# Met.net
KiCad netlist of a schematic drawn in EAGLE
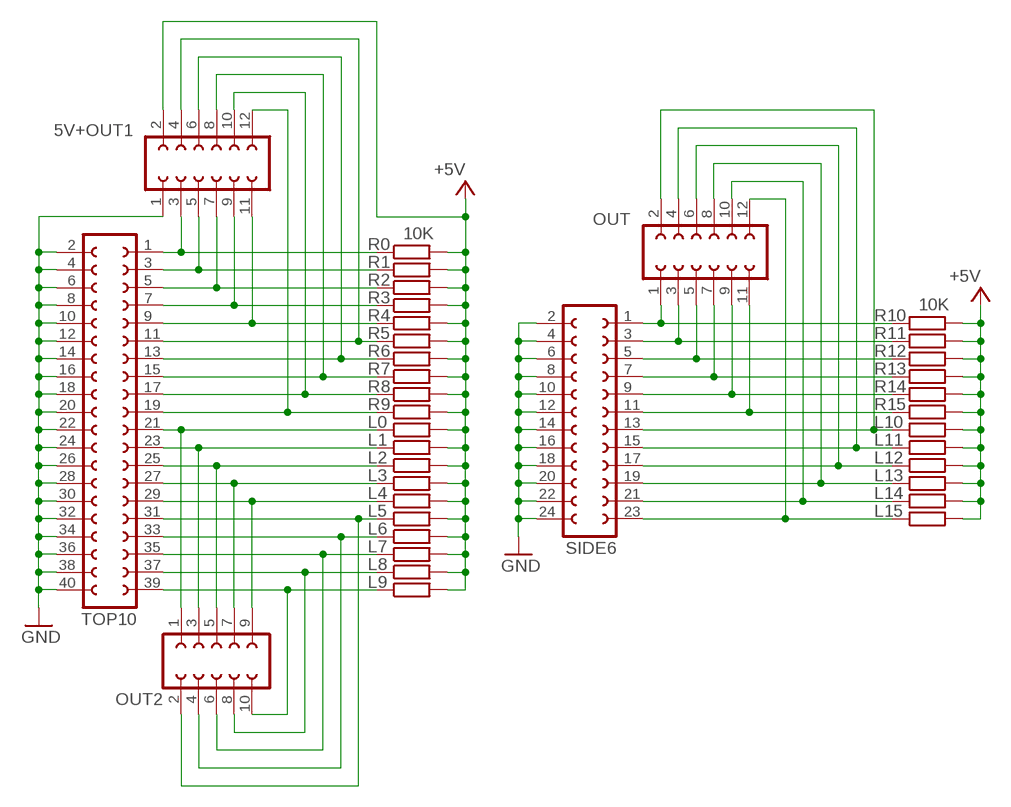
[diagram p0: schematic, sheet 1]

(export (version "E")
  (design (tool "Eeschema 10.0.6"))
  (components
    (comp (ref "5V+OUT1")
      (value "FE06-2")
      (footprint "eagle-import:FE06-2")
      (libsource (lib "eagle-import") (part "FE06-2"))
    )
    (comp (ref "L0")
      (value "R-EU_0207/10")
      (footprint "eagle-import:0207_10")
      (libsource (lib "eagle-import") (part "R-EU_0207/10"))
    )
    (comp (ref "L1")
      (value "R-EU_0207/10")
      (footprint "eagle-import:0207_10")
      (libsource (lib "eagle-import") (part "R-EU_0207/10"))
    )
    (comp (ref "L2")
      (value "R-EU_0207/10")
      (footprint "eagle-import:0207_10")
      (libsource (lib "eagle-import") (part "R-EU_0207/10"))
    )
    (comp (ref "L3")
      (value "R-EU_0207/10")
      (footprint "eagle-import:0207_10")
      (libsource (lib "eagle-import") (part "R-EU_0207/10"))
    )
    (comp (ref "L4")
      (value "R-EU_0207/10")
      (footprint "eagle-import:0207_10")
      (libsource (lib "eagle-import") (part "R-EU_0207/10"))
    )
    (comp (ref "L5")
      (value "R-EU_0207/10")
      (footprint "eagle-import:0207_10")
      (libsource (lib "eagle-import") (part "R-EU_0207/10"))
    )
    (comp (ref "L6")
      (value "R-EU_0207/10")
      (footprint "eagle-import:0207_10")
      (libsource (lib "eagle-import") (part "R-EU_0207/10"))
    )
    (comp (ref "L7")
      (value "R-EU_0207/10")
      (footprint "eagle-import:0207_10")
      (libsource (lib "eagle-import") (part "R-EU_0207/10"))
    )
    (comp (ref "L8")
      (value "R-EU_0207/10")
      (footprint "eagle-import:0207_10")
      (libsource (lib "eagle-import") (part "R-EU_0207/10"))
    )
    (comp (ref "L9")
      (value "R-EU_0207/10")
      (footprint "eagle-import:0207_10")
      (libsource (lib "eagle-import") (part "R-EU_0207/10"))
    )
    (comp (ref "L10")
      (value "R-EU_0207/10")
      (footprint "eagle-import:0207_10")
      (libsource (lib "eagle-import") (part "R-EU_0207/10"))
    )
    (comp (ref "L11")
      (value "R-EU_0207/10")
      (footprint "eagle-import:0207_10")
      (libsource (lib "eagle-import") (part "R-EU_0207/10"))
    )
    (comp (ref "L12")
      (value "R-EU_0207/10")
      (footprint "eagle-import:0207_10")
      (libsource (lib "eagle-import") (part "R-EU_0207/10"))
    )
    (comp (ref "L13")
      (value "R-EU_0207/10")
      (footprint "eagle-import:0207_10")
      (libsource (lib "eagle-import") (part "R-EU_0207/10"))
    )
    (comp (ref "L14")
      (value "R-EU_0207/10")
      (footprint "eagle-import:0207_10")
      (libsource (lib "eagle-import") (part "R-EU_0207/10"))
    )
    (comp (ref "L15")
      (value "R-EU_0207/10")
      (footprint "eagle-import:0207_10")
      (libsource (lib "eagle-import") (part "R-EU_0207/10"))
    )
    (comp (ref "OUT")
      (value "FE06-2")
      (footprint "eagle-import:FE06-2")
      (libsource (lib "eagle-import") (part "FE06-2"))
    )
    (comp (ref "OUT2")
      (value "FE05-2")
      (footprint "eagle-import:FE05-2")
      (libsource (lib "eagle-import") (part "FE05-2"))
    )
    (comp (ref "R0")
      (value "10K")
      (footprint "eagle-import:0207_10")
      (libsource (lib "eagle-import") (part "R-EU_0207/10"))
    )
    (comp (ref "R1")
      (value "R-EU_0207/10")
      (footprint "eagle-import:0207_10")
      (libsource (lib "eagle-import") (part "R-EU_0207/10"))
    )
    (comp (ref "R2")
      (value "R-EU_0207/10")
      (footprint "eagle-import:0207_10")
      (libsource (lib "eagle-import") (part "R-EU_0207/10"))
    )
    (comp (ref "R3")
      (value "R-EU_0207/10")
      (footprint "eagle-import:0207_10")
      (libsource (lib "eagle-import") (part "R-EU_0207/10"))
    )
    (comp (ref "R4")
      (value "R-EU_0207/10")
      (footprint "eagle-import:0207_10")
      (libsource (lib "eagle-import") (part "R-EU_0207/10"))
    )
    (comp (ref "R5")
      (value "R-EU_0207/10")
      (footprint "eagle-import:0207_10")
      (libsource (lib "eagle-import") (part "R-EU_0207/10"))
    )
    (comp (ref "R6")
      (value "R-EU_0207/10")
      (footprint "eagle-import:0207_10")
      (libsource (lib "eagle-import") (part "R-EU_0207/10"))
    )
    (comp (ref "R7")
      (value "R-EU_0207/10")
      (footprint "eagle-import:0207_10")
      (libsource (lib "eagle-import") (part "R-EU_0207/10"))
    )
    (comp (ref "R8")
      (value "R-EU_0207/10")
      (footprint "eagle-import:0207_10")
      (libsource (lib "eagle-import") (part "R-EU_0207/10"))
    )
    (comp (ref "R9")
      (value "R-EU_0207/10")
      (footprint "eagle-import:0207_10")
      (libsource (lib "eagle-import") (part "R-EU_0207/10"))
    )
    (comp (ref "R10")
      (value "10K")
      (footprint "eagle-import:0207_10")
      (libsource (lib "eagle-import") (part "R-EU_0207/10"))
    )
    (comp (ref "R11")
      (value "R-EU_0207/10")
      (footprint "eagle-import:0207_10")
      (libsource (lib "eagle-import") (part "R-EU_0207/10"))
    )
    (comp (ref "R12")
      (value "R-EU_0207/10")
      (footprint "eagle-import:0207_10")
      (libsource (lib "eagle-import") (part "R-EU_0207/10"))
    )
    (comp (ref "R13")
      (value "R-EU_0207/10")
      (footprint "eagle-import:0207_10")
      (libsource (lib "eagle-import") (part "R-EU_0207/10"))
    )
    (comp (ref "R14")
      (value "R-EU_0207/10")
      (footprint "eagle-import:0207_10")
      (libsource (lib "eagle-import") (part "R-EU_0207/10"))
    )
    (comp (ref "R15")
      (value "R-EU_0207/10")
      (footprint "eagle-import:0207_10")
      (libsource (lib "eagle-import") (part "R-EU_0207/10"))
    )
    (comp (ref "SIDE6")
      (value "FE12-2")
      (footprint "eagle-import:FE12-2")
      (libsource (lib "eagle-import") (part "FE12-2"))
    )
    (comp (ref "TOP10")
      (value "FE20-2")
      (footprint "eagle-import:FE20-2")
      (libsource (lib "eagle-import") (part "FE20-2"))
    )
  )
  (nets
    (net (code "1") (name "+5V") (class "Default")
      (node (ref "5V+OUT1") (pin "2") (pinfunction "2_2") (pintype "passive"))
      (node (ref "L0") (pin "2") (pinfunction "2_2") (pintype "passive"))
      (node (ref "L1") (pin "2") (pinfunction "2_2") (pintype "passive"))
      (node (ref "L10") (pin "2") (pinfunction "2_2") (pintype "passive"))
      (node (ref "L11") (pin "2") (pinfunction "2_2") (pintype "passive"))
      (node (ref "L12") (pin "2") (pinfunction "2_2") (pintype "passive"))
      (node (ref "L13") (pin "2") (pinfunction "2_2") (pintype "passive"))
      (node (ref "L14") (pin "2") (pinfunction "2_2") (pintype "passive"))
      (node (ref "L15") (pin "2") (pinfunction "2_2") (pintype "passive"))
      (node (ref "L2") (pin "2") (pinfunction "2_2") (pintype "passive"))
      (node (ref "L3") (pin "2") (pinfunction "2_2") (pintype "passive"))
      (node (ref "L4") (pin "2") (pinfunction "2_2") (pintype "passive"))
      (node (ref "L5") (pin "2") (pinfunction "2_2") (pintype "passive"))
      (node (ref "L6") (pin "2") (pinfunction "2_2") (pintype "passive"))
      (node (ref "L7") (pin "2") (pinfunction "2_2") (pintype "passive"))
      (node (ref "L8") (pin "2") (pinfunction "2_2") (pintype "passive"))
      (node (ref "L9") (pin "2") (pinfunction "2_2") (pintype "passive"))
      (node (ref "R0") (pin "2") (pinfunction "2_2") (pintype "passive"))
      (node (ref "R1") (pin "2") (pinfunction "2_2") (pintype "passive"))
      (node (ref "R10") (pin "2") (pinfunction "2_2") (pintype "passive"))
      (node (ref "R11") (pin "2") (pinfunction "2_2") (pintype "passive"))
      (node (ref "R12") (pin "2") (pinfunction "2_2") (pintype "passive"))
      (node (ref "R13") (pin "2") (pinfunction "2_2") (pintype "passive"))
      (node (ref "R14") (pin "2") (pinfunction "2_2") (pintype "passive"))
      (node (ref "R15") (pin "2") (pinfunction "2_2") (pintype "passive"))
      (node (ref "R2") (pin "2") (pinfunction "2_2") (pintype "passive"))
      (node (ref "R3") (pin "2") (pinfunction "2_2") (pintype "passive"))
      (node (ref "R4") (pin "2") (pinfunction "2_2") (pintype "passive"))
      (node (ref "R5") (pin "2") (pinfunction "2_2") (pintype "passive"))
      (node (ref "R6") (pin "2") (pinfunction "2_2") (pintype "passive"))
      (node (ref "R7") (pin "2") (pinfunction "2_2") (pintype "passive"))
      (node (ref "R8") (pin "2") (pinfunction "2_2") (pintype "passive"))
      (node (ref "R9") (pin "2") (pinfunction "2_2") (pintype "passive"))
    )
    (net (code "2") (name "GND") (class "Default")
      (node (ref "5V+OUT1") (pin "1") (pinfunction "1_1") (pintype "passive"))
      (node (ref "SIDE6") (pin "10") (pinfunction "10_10") (pintype "passive"))
      (node (ref "SIDE6") (pin "12") (pinfunction "12_12") (pintype "passive"))
      (node (ref "SIDE6") (pin "14") (pinfunction "14_14") (pintype "passive"))
      (node (ref "SIDE6") (pin "16") (pinfunction "16_16") (pintype "passive"))
      (node (ref "SIDE6") (pin "18") (pinfunction "18_18") (pintype "passive"))
      (node (ref "SIDE6") (pin "2") (pinfunction "2_2") (pintype "passive"))
      (node (ref "SIDE6") (pin "20") (pinfunction "20_20") (pintype "passive"))
      (node (ref "SIDE6") (pin "22") (pinfunction "22_22") (pintype "passive"))
      (node (ref "SIDE6") (pin "24") (pinfunction "24_24") (pintype "passive"))
      (node (ref "SIDE6") (pin "4") (pinfunction "4_4") (pintype "passive"))
      (node (ref "SIDE6") (pin "6") (pinfunction "6_6") (pintype "passive"))
      (node (ref "SIDE6") (pin "8") (pinfunction "8_8") (pintype "passive"))
      (node (ref "TOP10") (pin "10") (pinfunction "10_10") (pintype "passive"))
      (node (ref "TOP10") (pin "12") (pinfunction "12_12") (pintype "passive"))
      (node (ref "TOP10") (pin "14") (pinfunction "14_14") (pintype "passive"))
      (node (ref "TOP10") (pin "16") (pinfunction "16_16") (pintype "passive"))
      (node (ref "TOP10") (pin "18") (pinfunction "18_18") (pintype "passive"))
      (node (ref "TOP10") (pin "2") (pinfunction "2_2") (pintype "passive"))
      (node (ref "TOP10") (pin "20") (pinfunction "20_20") (pintype "passive"))
      (node (ref "TOP10") (pin "22") (pinfunction "22_22") (pintype "passive"))
      (node (ref "TOP10") (pin "24") (pinfunction "24_24") (pintype "passive"))
      (node (ref "TOP10") (pin "26") (pinfunction "26_26") (pintype "passive"))
      (node (ref "TOP10") (pin "28") (pinfunction "28_28") (pintype "passive"))
      (node (ref "TOP10") (pin "30") (pinfunction "30_30") (pintype "passive"))
      (node (ref "TOP10") (pin "32") (pinfunction "32_32") (pintype "passive"))
      (node (ref "TOP10") (pin "34") (pinfunction "34_34") (pintype "passive"))
      (node (ref "TOP10") (pin "36") (pinfunction "36_36") (pintype "passive"))
      (node (ref "TOP10") (pin "38") (pinfunction "38_38") (pintype "passive"))
      (node (ref "TOP10") (pin "4") (pinfunction "4_4") (pintype "passive"))
      (node (ref "TOP10") (pin "40") (pinfunction "40_40") (pintype "passive"))
      (node (ref "TOP10") (pin "6") (pinfunction "6_6") (pintype "passive"))
      (node (ref "TOP10") (pin "8") (pinfunction "8_8") (pintype "passive"))
    )
    (net (code "3") (name "Net-(5V+OUT1-Pad3)") (class "Default")
      (node (ref "5V+OUT1") (pin "3") (pinfunction "3_3") (pintype "passive"))
      (node (ref "R0") (pin "1") (pinfunction "1_1") (pintype "passive"))
      (node (ref "TOP10") (pin "1") (pinfunction "1_1") (pintype "passive"))
    )
    (net (code "4") (name "Net-(5V+OUT1-Pad4)") (class "Default")
      (node (ref "5V+OUT1") (pin "4") (pinfunction "4_4") (pintype "passive"))
      (node (ref "R5") (pin "1") (pinfunction "1_1") (pintype "passive"))
      (node (ref "TOP10") (pin "11") (pinfunction "11_11") (pintype "passive"))
    )
    (net (code "5") (name "Net-(5V+OUT1-Pad5)") (class "Default")
      (node (ref "5V+OUT1") (pin "5") (pinfunction "5_5") (pintype "passive"))
      (node (ref "R1") (pin "1") (pinfunction "1_1") (pintype "passive"))
      (node (ref "TOP10") (pin "3") (pinfunction "3_3") (pintype "passive"))
    )
    (net (code "6") (name "Net-(5V+OUT1-Pad6)") (class "Default")
      (node (ref "5V+OUT1") (pin "6") (pinfunction "6_6") (pintype "passive"))
      (node (ref "R6") (pin "1") (pinfunction "1_1") (pintype "passive"))
      (node (ref "TOP10") (pin "13") (pinfunction "13_13") (pintype "passive"))
    )
    (net (code "7") (name "Net-(5V+OUT1-Pad7)") (class "Default")
      (node (ref "5V+OUT1") (pin "7") (pinfunction "7_7") (pintype "passive"))
      (node (ref "R2") (pin "1") (pinfunction "1_1") (pintype "passive"))
      (node (ref "TOP10") (pin "5") (pinfunction "5_5") (pintype "passive"))
    )
    (net (code "8") (name "Net-(5V+OUT1-Pad8)") (class "Default")
      (node (ref "5V+OUT1") (pin "8") (pinfunction "8_8") (pintype "passive"))
      (node (ref "R7") (pin "1") (pinfunction "1_1") (pintype "passive"))
      (node (ref "TOP10") (pin "15") (pinfunction "15_15") (pintype "passive"))
    )
    (net (code "9") (name "Net-(5V+OUT1-Pad9)") (class "Default")
      (node (ref "5V+OUT1") (pin "9") (pinfunction "9_9") (pintype "passive"))
      (node (ref "R3") (pin "1") (pinfunction "1_1") (pintype "passive"))
      (node (ref "TOP10") (pin "7") (pinfunction "7_7") (pintype "passive"))
    )
    (net (code "10") (name "Net-(5V+OUT1-Pad10)") (class "Default")
      (node (ref "5V+OUT1") (pin "10") (pinfunction "10_10") (pintype "passive"))
      (node (ref "R8") (pin "1") (pinfunction "1_1") (pintype "passive"))
      (node (ref "TOP10") (pin "17") (pinfunction "17_17") (pintype "passive"))
    )
    (net (code "11") (name "Net-(5V+OUT1-Pad11)") (class "Default")
      (node (ref "5V+OUT1") (pin "11") (pinfunction "11_11") (pintype "passive"))
      (node (ref "R4") (pin "1") (pinfunction "1_1") (pintype "passive"))
      (node (ref "TOP10") (pin "9") (pinfunction "9_9") (pintype "passive"))
    )
    (net (code "12") (name "Net-(5V+OUT1-Pad12)") (class "Default")
      (node (ref "5V+OUT1") (pin "12") (pinfunction "12_12") (pintype "passive"))
      (node (ref "R9") (pin "1") (pinfunction "1_1") (pintype "passive"))
      (node (ref "TOP10") (pin "19") (pinfunction "19_19") (pintype "passive"))
    )
    (net (code "13") (name "Net-(L0-Pad1)") (class "Default")
      (node (ref "L0") (pin "1") (pinfunction "1_1") (pintype "passive"))
      (node (ref "OUT2") (pin "1") (pinfunction "1_1") (pintype "passive"))
      (node (ref "TOP10") (pin "21") (pinfunction "21_21") (pintype "passive"))
    )
    (net (code "14") (name "Net-(L1-Pad1)") (class "Default")
      (node (ref "L1") (pin "1") (pinfunction "1_1") (pintype "passive"))
      (node (ref "OUT2") (pin "3") (pinfunction "3_3") (pintype "passive"))
      (node (ref "TOP10") (pin "23") (pinfunction "23_23") (pintype "passive"))
    )
    (net (code "15") (name "Net-(L2-Pad1)") (class "Default")
      (node (ref "L2") (pin "1") (pinfunction "1_1") (pintype "passive"))
      (node (ref "OUT2") (pin "5") (pinfunction "5_5") (pintype "passive"))
      (node (ref "TOP10") (pin "25") (pinfunction "25_25") (pintype "passive"))
    )
    (net (code "16") (name "Net-(L3-Pad1)") (class "Default")
      (node (ref "L3") (pin "1") (pinfunction "1_1") (pintype "passive"))
      (node (ref "OUT2") (pin "7") (pinfunction "7_7") (pintype "passive"))
      (node (ref "TOP10") (pin "27") (pinfunction "27_27") (pintype "passive"))
    )
    (net (code "17") (name "Net-(L4-Pad1)") (class "Default")
      (node (ref "L4") (pin "1") (pinfunction "1_1") (pintype "passive"))
      (node (ref "OUT2") (pin "9") (pinfunction "9_9") (pintype "passive"))
      (node (ref "TOP10") (pin "29") (pinfunction "29_29") (pintype "passive"))
    )
    (net (code "18") (name "Net-(L5-Pad1)") (class "Default")
      (node (ref "L5") (pin "1") (pinfunction "1_1") (pintype "passive"))
      (node (ref "OUT2") (pin "2") (pinfunction "2_2") (pintype "passive"))
      (node (ref "TOP10") (pin "31") (pinfunction "31_31") (pintype "passive"))
    )
    (net (code "19") (name "Net-(L6-Pad1)") (class "Default")
      (node (ref "L6") (pin "1") (pinfunction "1_1") (pintype "passive"))
      (node (ref "OUT2") (pin "4") (pinfunction "4_4") (pintype "passive"))
      (node (ref "TOP10") (pin "33") (pinfunction "33_33") (pintype "passive"))
    )
    (net (code "20") (name "Net-(L7-Pad1)") (class "Default")
      (node (ref "L7") (pin "1") (pinfunction "1_1") (pintype "passive"))
      (node (ref "OUT2") (pin "6") (pinfunction "6_6") (pintype "passive"))
      (node (ref "TOP10") (pin "35") (pinfunction "35_35") (pintype "passive"))
    )
    (net (code "21") (name "Net-(L8-Pad1)") (class "Default")
      (node (ref "L8") (pin "1") (pinfunction "1_1") (pintype "passive"))
      (node (ref "OUT2") (pin "8") (pinfunction "8_8") (pintype "passive"))
      (node (ref "TOP10") (pin "37") (pinfunction "37_37") (pintype "passive"))
    )
    (net (code "22") (name "Net-(L9-Pad1)") (class "Default")
      (node (ref "L9") (pin "1") (pinfunction "1_1") (pintype "passive"))
      (node (ref "OUT2") (pin "10") (pinfunction "10_10") (pintype "passive"))
      (node (ref "TOP10") (pin "39") (pinfunction "39_39") (pintype "passive"))
    )
    (net (code "23") (name "Net-(L10-Pad1)") (class "Default")
      (node (ref "L10") (pin "1") (pinfunction "1_1") (pintype "passive"))
      (node (ref "OUT") (pin "2") (pinfunction "2_2") (pintype "passive"))
      (node (ref "SIDE6") (pin "13") (pinfunction "13_13") (pintype "passive"))
    )
    (net (code "24") (name "Net-(L11-Pad1)") (class "Default")
      (node (ref "L11") (pin "1") (pinfunction "1_1") (pintype "passive"))
      (node (ref "OUT") (pin "4") (pinfunction "4_4") (pintype "passive"))
      (node (ref "SIDE6") (pin "15") (pinfunction "15_15") (pintype "passive"))
    )
    (net (code "25") (name "Net-(L12-Pad1)") (class "Default")
      (node (ref "L12") (pin "1") (pinfunction "1_1") (pintype "passive"))
      (node (ref "OUT") (pin "6") (pinfunction "6_6") (pintype "passive"))
      (node (ref "SIDE6") (pin "17") (pinfunction "17_17") (pintype "passive"))
    )
    (net (code "26") (name "Net-(L13-Pad1)") (class "Default")
      (node (ref "L13") (pin "1") (pinfunction "1_1") (pintype "passive"))
      (node (ref "OUT") (pin "8") (pinfunction "8_8") (pintype "passive"))
      (node (ref "SIDE6") (pin "19") (pinfunction "19_19") (pintype "passive"))
    )
    (net (code "27") (name "Net-(L14-Pad1)") (class "Default")
      (node (ref "L14") (pin "1") (pinfunction "1_1") (pintype "passive"))
      (node (ref "OUT") (pin "10") (pinfunction "10_10") (pintype "passive"))
      (node (ref "SIDE6") (pin "21") (pinfunction "21_21") (pintype "passive"))
    )
    (net (code "28") (name "Net-(L15-Pad1)") (class "Default")
      (node (ref "L15") (pin "1") (pinfunction "1_1") (pintype "passive"))
      (node (ref "OUT") (pin "12") (pinfunction "12_12") (pintype "passive"))
      (node (ref "SIDE6") (pin "23") (pinfunction "23_23") (pintype "passive"))
    )
    (net (code "29") (name "Net-(OUT-Pad1)") (class "Default")
      (node (ref "OUT") (pin "1") (pinfunction "1_1") (pintype "passive"))
      (node (ref "R10") (pin "1") (pinfunction "1_1") (pintype "passive"))
      (node (ref "SIDE6") (pin "1") (pinfunction "1_1") (pintype "passive"))
    )
    (net (code "30") (name "Net-(OUT-Pad3)") (class "Default")
      (node (ref "OUT") (pin "3") (pinfunction "3_3") (pintype "passive"))
      (node (ref "R11") (pin "1") (pinfunction "1_1") (pintype "passive"))
      (node (ref "SIDE6") (pin "3") (pinfunction "3_3") (pintype "passive"))
    )
    (net (code "31") (name "Net-(OUT-Pad5)") (class "Default")
      (node (ref "OUT") (pin "5") (pinfunction "5_5") (pintype "passive"))
      (node (ref "R12") (pin "1") (pinfunction "1_1") (pintype "passive"))
      (node (ref "SIDE6") (pin "5") (pinfunction "5_5") (pintype "passive"))
    )
    (net (code "32") (name "Net-(OUT-Pad7)") (class "Default")
      (node (ref "OUT") (pin "7") (pinfunction "7_7") (pintype "passive"))
      (node (ref "R13") (pin "1") (pinfunction "1_1") (pintype "passive"))
      (node (ref "SIDE6") (pin "7") (pinfunction "7_7") (pintype "passive"))
    )
    (net (code "33") (name "Net-(OUT-Pad9)") (class "Default")
      (node (ref "OUT") (pin "9") (pinfunction "9_9") (pintype "passive"))
      (node (ref "R14") (pin "1") (pinfunction "1_1") (pintype "passive"))
      (node (ref "SIDE6") (pin "9") (pinfunction "9_9") (pintype "passive"))
    )
    (net (code "34") (name "Net-(OUT-Pad11)") (class "Default")
      (node (ref "OUT") (pin "11") (pinfunction "11_11") (pintype "passive"))
      (node (ref "R15") (pin "1") (pinfunction "1_1") (pintype "passive"))
      (node (ref "SIDE6") (pin "11") (pinfunction "11_11") (pintype "passive"))
    )
  )
)
